# tests.net
KiCad netlist of a schematic drawn in EAGLE
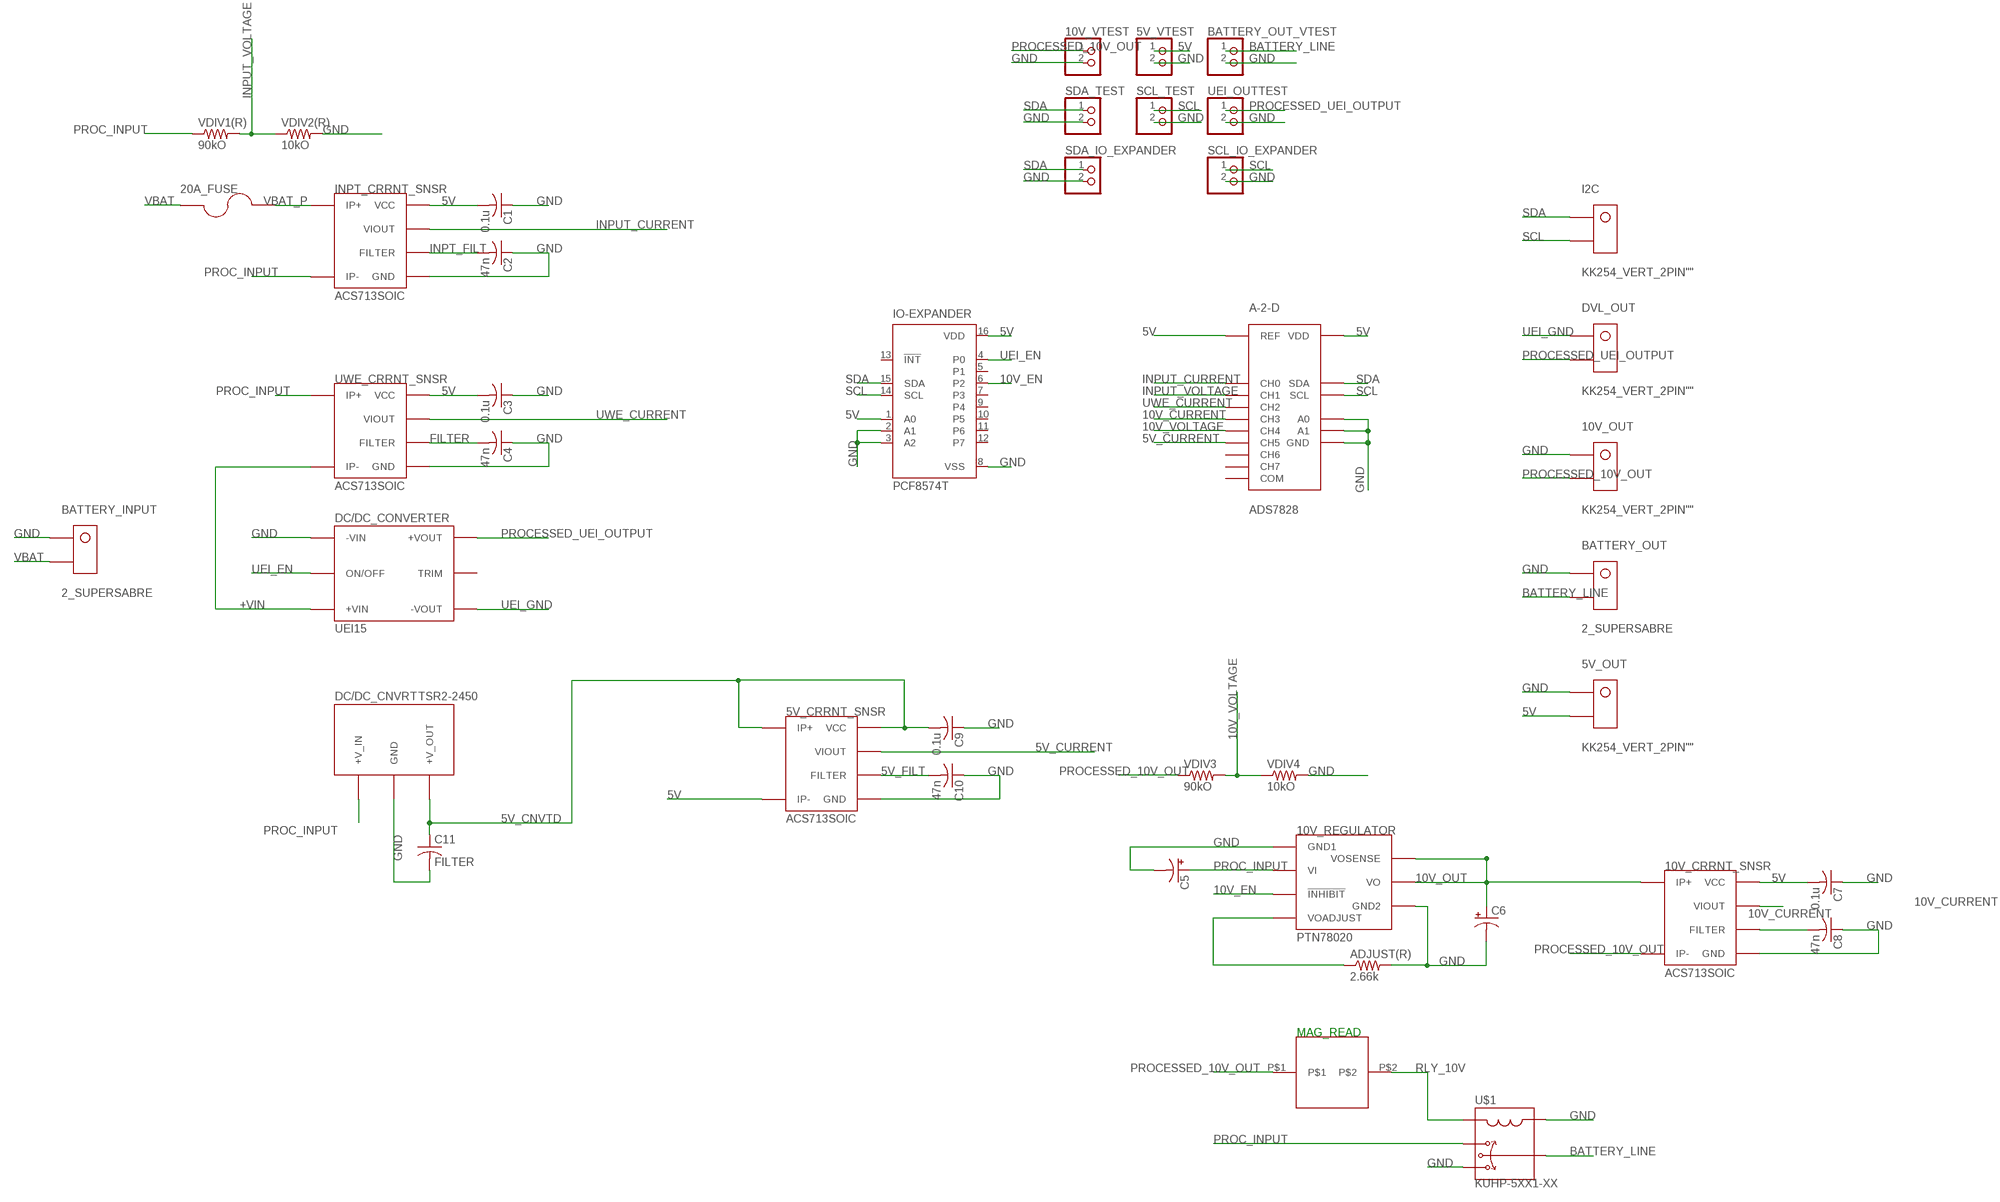
[diagram p0: schematic, sheet 1]

(export (version "E")
  (design (tool "Eeschema 10.0.6"))
  (components
    (comp (ref "5V_CRRNT_SNSR")
      (value "ACS713SOIC")
      (footprint "eagle-import:ACS713-SOIC")
      (libsource (lib "eagle-import") (part "ACS713SOIC"))
    )
    (comp (ref "5V_OUT")
      (value "KK254_VERT_2PIN\"\"")
      (footprint "eagle-import:KK254_VERT_2PIN")
      (libsource (lib "eagle-import") (part "KK254_VERT_2PIN{dblquote}{dblquote}"))
    )
    (comp (ref "5V_VTEST")
      (value "PINHD-1X2")
      (footprint "eagle-import:1X02")
      (libsource (lib "eagle-import") (part "PINHD-1X2"))
    )
    (comp (ref "10V_CRRNT_SNSR")
      (value "ACS713SOIC")
      (footprint "eagle-import:ACS713-SOIC")
      (libsource (lib "eagle-import") (part "ACS713SOIC"))
    )
    (comp (ref "10V_OUT")
      (value "KK254_VERT_2PIN\"\"")
      (footprint "eagle-import:KK254_VERT_2PIN")
      (libsource (lib "eagle-import") (part "KK254_VERT_2PIN{dblquote}{dblquote}"))
    )
    (comp (ref "10V_REGULATOR")
      (value "PTN78020")
      (footprint "eagle-import:PTN")
      (libsource (lib "eagle-import") (part "PTN78020"))
    )
    (comp (ref "10V_VTEST")
      (value "PINHD-1X2")
      (footprint "eagle-import:1X02")
      (libsource (lib "eagle-import") (part "PINHD-1X2"))
    )
    (comp (ref "20A_FUSE")
      (value "BOWED-1.25\"-FUSECLIPS")
      (footprint "eagle-import:1.25__FUSECLIPS")
      (libsource (lib "eagle-import") (part "BOWED-1.25{dblquote}-FUSECLIPS"))
    )
    (comp (ref "A-2-D")
      (value "ADS7828")
      (footprint "eagle-import:TSSOP16")
      (libsource (lib "eagle-import") (part "ADS7828"))
    )
    (comp (ref "ADJUST(R)")
      (value "2.66k")
      (footprint "eagle-import:R0805")
      (libsource (lib "eagle-import") (part "R-US_R0805"))
    )
    (comp (ref "BATTERY_INPUT")
      (value "2_SUPERSABRE")
      (footprint "eagle-import:SUPERSABRE_2CIRCUIT")
      (libsource (lib "eagle-import") (part "2_SUPERSABRE"))
    )
    (comp (ref "BATTERY_OUT")
      (value "2_SUPERSABRE")
      (footprint "eagle-import:SUPERSABRE_2CIRCUIT")
      (libsource (lib "eagle-import") (part "2_SUPERSABRE"))
    )
    (comp (ref "BATTERY_OUT_VTEST")
      (value "PINHD-1X2")
      (footprint "eagle-import:1X02")
      (libsource (lib "eagle-import") (part "PINHD-1X2"))
    )
    (comp (ref "C1")
      (value "0.1u")
      (footprint "eagle-import:C0805")
      (libsource (lib "eagle-import") (part "C-USC0805"))
    )
    (comp (ref "C2")
      (value "47n")
      (footprint "eagle-import:C0805")
      (libsource (lib "eagle-import") (part "C-USC0805"))
    )
    (comp (ref "C3")
      (value "0.1u")
      (footprint "eagle-import:C0805")
      (libsource (lib "eagle-import") (part "C-USC0805"))
    )
    (comp (ref "C4")
      (value "47n")
      (footprint "eagle-import:C0805")
      (libsource (lib "eagle-import") (part "C-USC0805"))
    )
    (comp (ref "C5")
      (value "CPOL-US")
      (footprint "eagle-import:PANASONIC_A_TYPE_M")
      (libsource (lib "eagle-import") (part "CPOL-US"))
    )
    (comp (ref "C6")
      (value "CPOL-US")
      (footprint "eagle-import:PANASONIC_A_TYPE_M")
      (libsource (lib "eagle-import") (part "CPOL-US"))
    )
    (comp (ref "C7")
      (value "0.1u")
      (footprint "eagle-import:C0805")
      (libsource (lib "eagle-import") (part "C-USC0805"))
    )
    (comp (ref "C8")
      (value "47n")
      (footprint "eagle-import:C0805")
      (libsource (lib "eagle-import") (part "C-USC0805"))
    )
    (comp (ref "C9")
      (value "0.1u")
      (footprint "eagle-import:C0805")
      (libsource (lib "eagle-import") (part "C-USC0805"))
    )
    (comp (ref "C10")
      (value "47n")
      (footprint "eagle-import:C0805")
      (libsource (lib "eagle-import") (part "C-USC0805"))
    )
    (comp (ref "C11")
      (value "FILTER")
      (footprint "eagle-import:C0805")
      (libsource (lib "eagle-import") (part "C-USC0805"))
    )
    (comp (ref "DC/DC_CNVRT")
      (value "TSR2-2450")
      (footprint "eagle-import:TSR2")
      (libsource (lib "eagle-import") (part "TSR2-2450"))
    )
    (comp (ref "DC/DC_CONVERTER")
      (value "UEI15")
      (footprint "eagle-import:UEI15")
      (libsource (lib "eagle-import") (part "UEI15"))
    )
    (comp (ref "DVL_OUT")
      (value "KK254_VERT_2PIN\"\"")
      (footprint "eagle-import:KK254_VERT_2PIN")
      (libsource (lib "eagle-import") (part "KK254_VERT_2PIN{dblquote}{dblquote}"))
    )
    (comp (ref "I2C")
      (value "KK254_VERT_2PIN\"\"")
      (footprint "eagle-import:KK254_VERT_2PIN")
      (libsource (lib "eagle-import") (part "KK254_VERT_2PIN{dblquote}{dblquote}"))
    )
    (comp (ref "INPT_CRRNT_SNSR")
      (value "ACS713SOIC")
      (footprint "eagle-import:ACS713-SOIC")
      (libsource (lib "eagle-import") (part "ACS713SOIC"))
    )
    (comp (ref "IO-EXPANDER")
      (value "PCF8574T")
      (footprint "eagle-import:SO16W")
      (fields (field (name "MPN") "PCF8574T/3,512"))
      (libsource (lib "eagle-import") (part "PCF8574T"))
    )
    (comp (ref "MAGREAD")
      (value "HE151TR-ND")
      (footprint "eagle-import:HE151TR-ND")
      (libsource (lib "eagle-import") (part "HE151TR-ND"))
    )
    (comp (ref "SCL_IO_EXPANDER")
      (value "PINHD-1X2")
      (footprint "eagle-import:1X02")
      (libsource (lib "eagle-import") (part "PINHD-1X2"))
    )
    (comp (ref "SCL_TEST")
      (value "PINHD-1X2")
      (footprint "eagle-import:1X02")
      (libsource (lib "eagle-import") (part "PINHD-1X2"))
    )
    (comp (ref "SDA_IO_EXPANDER")
      (value "PINHD-1X2")
      (footprint "eagle-import:1X02")
      (libsource (lib "eagle-import") (part "PINHD-1X2"))
    )
    (comp (ref "SDA_TEST")
      (value "PINHD-1X2")
      (footprint "eagle-import:1X02")
      (libsource (lib "eagle-import") (part "PINHD-1X2"))
    )
    (comp (ref "U$1")
      (value "KUHP-5XX1-XX")
      (footprint "eagle-import:KUHP_6.35MM-QUICK-CONNECT")
      (libsource (lib "eagle-import") (part "KUHP-5XX1-XX"))
    )
    (comp (ref "UEI_OUTTEST")
      (value "PINHD-1X2")
      (footprint "eagle-import:1X02")
      (libsource (lib "eagle-import") (part "PINHD-1X2"))
    )
    (comp (ref "UWE_CRRNT_SNSR")
      (value "ACS713SOIC")
      (footprint "eagle-import:ACS713-SOIC")
      (libsource (lib "eagle-import") (part "ACS713SOIC"))
    )
    (comp (ref "VDIV1(R)")
      (value "90kO")
      (footprint "eagle-import:R0805")
      (libsource (lib "eagle-import") (part "R-US_R0805"))
    )
    (comp (ref "VDIV2(R)")
      (value "10kO")
      (footprint "eagle-import:R0805")
      (libsource (lib "eagle-import") (part "R-US_R0805"))
    )
    (comp (ref "VDIV3")
      (value "90kO")
      (footprint "eagle-import:R0805")
      (libsource (lib "eagle-import") (part "R-US_R0805"))
    )
    (comp (ref "VDIV4")
      (value "10kO")
      (footprint "eagle-import:R0805")
      (libsource (lib "eagle-import") (part "R-US_R0805"))
    )
  )
  (nets
    (net (code "1") (name "/+VIN") (class "Default")
      (node (ref "DC/DC_CONVERTER") (pin "+VIN") (pinfunction "+VIN_+VIN") (pintype "power_in"))
      (node (ref "UWE_CRRNT_SNSR") (pin "P$3") (pinfunction "IP-_P$3") (pintype "bidirectional"))
      (node (ref "UWE_CRRNT_SNSR") (pin "P$4") (pinfunction "IP-_P$4") (pintype "bidirectional"))
    )
    (net (code "2") (name "/5V") (class "Default")
      (node (ref "10V_CRRNT_SNSR") (pin "P$8") (pinfunction "VCC_P$8") (pintype "bidirectional"))
      (node (ref "5V_CRRNT_SNSR") (pin "P$3") (pinfunction "IP-_P$3") (pintype "bidirectional"))
      (node (ref "5V_CRRNT_SNSR") (pin "P$4") (pinfunction "IP-_P$4") (pintype "bidirectional"))
      (node (ref "5V_OUT") (pin "P$2") (pinfunction "P$2_P$2") (pintype "bidirectional"))
      (node (ref "5V_VTEST") (pin "1") (pinfunction "1_1") (pintype "passive"))
      (node (ref "A-2-D") (pin "10") (pinfunction "REF_10") (pintype "bidirectional"))
      (node (ref "A-2-D") (pin "16") (pinfunction "VDD_16") (pintype "bidirectional"))
      (node (ref "C1") (pin "2") (pinfunction "2_2") (pintype "passive"))
      (node (ref "C3") (pin "2") (pinfunction "2_2") (pintype "passive"))
      (node (ref "C7") (pin "2") (pinfunction "2_2") (pintype "passive"))
      (node (ref "INPT_CRRNT_SNSR") (pin "P$8") (pinfunction "VCC_P$8") (pintype "bidirectional"))
      (node (ref "IO-EXPANDER") (pin "1") (pinfunction "A0_1") (pintype "input"))
      (node (ref "IO-EXPANDER") (pin "16") (pinfunction "VDD_16") (pintype "power_in"))
      (node (ref "UWE_CRRNT_SNSR") (pin "P$8") (pinfunction "VCC_P$8") (pintype "bidirectional"))
    )
    (net (code "3") (name "/5V_CNVTD") (class "Default")
      (node (ref "5V_CRRNT_SNSR") (pin "P$1") (pinfunction "IP+_P$1") (pintype "bidirectional"))
      (node (ref "5V_CRRNT_SNSR") (pin "P$2") (pinfunction "IP+_P$2") (pintype "bidirectional"))
      (node (ref "5V_CRRNT_SNSR") (pin "P$8") (pinfunction "VCC_P$8") (pintype "bidirectional"))
      (node (ref "C11") (pin "1") (pinfunction "1_1") (pintype "passive"))
      (node (ref "C9") (pin "2") (pinfunction "2_2") (pintype "passive"))
      (node (ref "DC/DC_CNVRT") (pin "3") (pinfunction "+V_OUT_3") (pintype "power_in"))
    )
    (net (code "4") (name "/5V_CURRENT") (class "Default")
      (node (ref "5V_CRRNT_SNSR") (pin "P$7") (pinfunction "VIOUT_P$7") (pintype "bidirectional"))
      (node (ref "A-2-D") (pin "6") (pinfunction "CH5_6") (pintype "bidirectional"))
    )
    (net (code "5") (name "/5V_FILT") (class "Default")
      (node (ref "5V_CRRNT_SNSR") (pin "P$6") (pinfunction "FILTER_P$6") (pintype "bidirectional"))
      (node (ref "C10") (pin "2") (pinfunction "2_2") (pintype "passive"))
    )
    (net (code "6") (name "/10V_CURRENT") (class "Default")
      (node (ref "10V_CRRNT_SNSR") (pin "P$7") (pinfunction "VIOUT_P$7") (pintype "bidirectional"))
      (node (ref "A-2-D") (pin "4") (pinfunction "CH3_4") (pintype "bidirectional"))
    )
    (net (code "7") (name "/10V_EN") (class "Default")
      (node (ref "10V_REGULATOR") (pin "INHIBIT") (pinfunction "~{INHIBIT}_INHIBIT") (pintype "bidirectional"))
      (node (ref "IO-EXPANDER") (pin "6") (pinfunction "P2_6") (pintype "bidirectional"))
    )
    (net (code "8") (name "/10V_OUT") (class "Default")
      (node (ref "10V_CRRNT_SNSR") (pin "P$1") (pinfunction "IP+_P$1") (pintype "bidirectional"))
      (node (ref "10V_CRRNT_SNSR") (pin "P$2") (pinfunction "IP+_P$2") (pintype "bidirectional"))
      (node (ref "10V_REGULATOR") (pin "SENSE") (pinfunction "VOSENSE_SENSE") (pintype "bidirectional"))
      (node (ref "10V_REGULATOR") (pin "VOUT") (pinfunction "VO_VOUT") (pintype "bidirectional"))
      (node (ref "C6") (pin "+") (pinfunction "+_+") (pintype "passive"))
    )
    (net (code "9") (name "/10V_VOLTAGE") (class "Default")
      (node (ref "A-2-D") (pin "5") (pinfunction "CH4_5") (pintype "bidirectional"))
      (node (ref "VDIV3") (pin "2") (pinfunction "2_2") (pintype "passive"))
      (node (ref "VDIV4") (pin "1") (pinfunction "1_1") (pintype "passive"))
    )
    (net (code "10") (name "/BATTERY_LINE") (class "Default")
      (node (ref "BATTERY_OUT") (pin "P$2") (pinfunction "P$2_P$2") (pintype "bidirectional"))
      (node (ref "BATTERY_OUT_VTEST") (pin "1") (pinfunction "1_1") (pintype "passive"))
      (node (ref "U$1") (pin "7A") (pinfunction "7_7A") (pintype "bidirectional"))
      (node (ref "U$1") (pin "7B") (pinfunction "7_7B") (pintype "bidirectional"))
    )
    (net (code "11") (name "/FILTER") (class "Default")
      (node (ref "C4") (pin "2") (pinfunction "2_2") (pintype "passive"))
      (node (ref "UWE_CRRNT_SNSR") (pin "P$6") (pinfunction "FILTER_P$6") (pintype "bidirectional"))
    )
    (net (code "12") (name "/GND") (class "Default")
      (node (ref "10V_CRRNT_SNSR") (pin "P$5") (pinfunction "GND_P$5") (pintype "bidirectional"))
      (node (ref "10V_OUT") (pin "P$1") (pinfunction "P$1_P$1") (pintype "bidirectional"))
      (node (ref "10V_REGULATOR") (pin "GND1") (pinfunction "GND1_GND1") (pintype "bidirectional"))
      (node (ref "10V_REGULATOR") (pin "GND2") (pinfunction "GND2_GND2") (pintype "bidirectional"))
      (node (ref "10V_VTEST") (pin "2") (pinfunction "2_2") (pintype "passive"))
      (node (ref "5V_CRRNT_SNSR") (pin "P$5") (pinfunction "GND_P$5") (pintype "bidirectional"))
      (node (ref "5V_OUT") (pin "P$1") (pinfunction "P$1_P$1") (pintype "bidirectional"))
      (node (ref "5V_VTEST") (pin "2") (pinfunction "2_2") (pintype "passive"))
      (node (ref "A-2-D") (pin "12") (pinfunction "A0_12") (pintype "bidirectional"))
      (node (ref "A-2-D") (pin "13") (pinfunction "A1_13") (pintype "bidirectional"))
      (node (ref "A-2-D") (pin "9") (pinfunction "GND_9") (pintype "bidirectional"))
      (node (ref "ADJUST(R)") (pin "2") (pinfunction "2_2") (pintype "passive"))
      (node (ref "BATTERY_INPUT") (pin "P$1") (pinfunction "P$1_P$1") (pintype "bidirectional"))
      (node (ref "BATTERY_OUT") (pin "P$1") (pinfunction "P$1_P$1") (pintype "bidirectional"))
      (node (ref "BATTERY_OUT_VTEST") (pin "2") (pinfunction "2_2") (pintype "passive"))
      (node (ref "C1") (pin "1") (pinfunction "1_1") (pintype "passive"))
      (node (ref "C10") (pin "1") (pinfunction "1_1") (pintype "passive"))
      (node (ref "C11") (pin "2") (pinfunction "2_2") (pintype "passive"))
      (node (ref "C2") (pin "1") (pinfunction "1_1") (pintype "passive"))
      (node (ref "C3") (pin "1") (pinfunction "1_1") (pintype "passive"))
      (node (ref "C4") (pin "1") (pinfunction "1_1") (pintype "passive"))
      (node (ref "C5") (pin "-") (pinfunction "-_-") (pintype "passive"))
      (node (ref "C6") (pin "-") (pinfunction "-_-") (pintype "passive"))
      (node (ref "C7") (pin "1") (pinfunction "1_1") (pintype "passive"))
      (node (ref "C8") (pin "1") (pinfunction "1_1") (pintype "passive"))
      (node (ref "C9") (pin "1") (pinfunction "1_1") (pintype "passive"))
      (node (ref "DC/DC_CNVRT") (pin "2") (pinfunction "GND_2") (pintype "power_in"))
      (node (ref "DC/DC_CONVERTER") (pin "-VIN") (pinfunction "-VIN_-VIN") (pintype "power_in"))
      (node (ref "INPT_CRRNT_SNSR") (pin "P$5") (pinfunction "GND_P$5") (pintype "bidirectional"))
      (node (ref "IO-EXPANDER") (pin "2") (pinfunction "A1_2") (pintype "input"))
      (node (ref "IO-EXPANDER") (pin "3") (pinfunction "A2_3") (pintype "input"))
      (node (ref "IO-EXPANDER") (pin "8") (pinfunction "VSS_8") (pintype "power_in"))
      (node (ref "SCL_IO_EXPANDER") (pin "2") (pinfunction "2_2") (pintype "passive"))
      (node (ref "SCL_TEST") (pin "2") (pinfunction "2_2") (pintype "passive"))
      (node (ref "SDA_IO_EXPANDER") (pin "2") (pinfunction "2_2") (pintype "passive"))
      (node (ref "SDA_TEST") (pin "2") (pinfunction "2_2") (pintype "passive"))
      (node (ref "U$1") (pin "5A") (pinfunction "5_5A") (pintype "bidirectional"))
      (node (ref "U$1") (pin "5B") (pinfunction "5_5B") (pintype "bidirectional"))
      (node (ref "U$1") (pin "AA") (pinfunction "A_AA") (pintype "bidirectional"))
      (node (ref "U$1") (pin "AB") (pinfunction "A_AB") (pintype "bidirectional"))
      (node (ref "UEI_OUTTEST") (pin "2") (pinfunction "2_2") (pintype "passive"))
      (node (ref "UWE_CRRNT_SNSR") (pin "P$5") (pinfunction "GND_P$5") (pintype "bidirectional"))
      (node (ref "VDIV2(R)") (pin "2") (pinfunction "2_2") (pintype "passive"))
      (node (ref "VDIV4") (pin "2") (pinfunction "2_2") (pintype "passive"))
    )
    (net (code "13") (name "/INPT_FILT") (class "Default")
      (node (ref "C2") (pin "2") (pinfunction "2_2") (pintype "passive"))
      (node (ref "INPT_CRRNT_SNSR") (pin "P$6") (pinfunction "FILTER_P$6") (pintype "bidirectional"))
    )
    (net (code "14") (name "/INPUT_CURRENT") (class "Default")
      (node (ref "A-2-D") (pin "1") (pinfunction "CH0_1") (pintype "bidirectional"))
      (node (ref "INPT_CRRNT_SNSR") (pin "P$7") (pinfunction "VIOUT_P$7") (pintype "bidirectional"))
    )
    (net (code "15") (name "/INPUT_VOLTAGE") (class "Default")
      (node (ref "A-2-D") (pin "2") (pinfunction "CH1_2") (pintype "bidirectional"))
      (node (ref "VDIV1(R)") (pin "2") (pinfunction "2_2") (pintype "passive"))
      (node (ref "VDIV2(R)") (pin "1") (pinfunction "1_1") (pintype "passive"))
    )
    (net (code "16") (name "/PROCESSED_10V_OUT") (class "Default")
      (node (ref "10V_CRRNT_SNSR") (pin "P$3") (pinfunction "IP-_P$3") (pintype "bidirectional"))
      (node (ref "10V_CRRNT_SNSR") (pin "P$4") (pinfunction "IP-_P$4") (pintype "bidirectional"))
      (node (ref "10V_OUT") (pin "P$2") (pinfunction "P$2_P$2") (pintype "bidirectional"))
      (node (ref "10V_VTEST") (pin "1") (pinfunction "1_1") (pintype "passive"))
      (node (ref "MAGREAD") (pin "P$1") (pinfunction "P$1_P$1") (pintype "bidirectional"))
      (node (ref "VDIV3") (pin "1") (pinfunction "1_1") (pintype "passive"))
    )
    (net (code "17") (name "/PROCESSED_UEI_OUTPUT") (class "Default")
      (node (ref "DC/DC_CONVERTER") (pin "+VOUT") (pinfunction "+VOUT_+VOUT") (pintype "power_in"))
      (node (ref "DVL_OUT") (pin "P$2") (pinfunction "P$2_P$2") (pintype "bidirectional"))
      (node (ref "UEI_OUTTEST") (pin "1") (pinfunction "1_1") (pintype "passive"))
    )
    (net (code "18") (name "/PROC_INPUT") (class "Default")
      (node (ref "10V_REGULATOR") (pin "VIN") (pinfunction "VI_VIN") (pintype "bidirectional"))
      (node (ref "C5") (pin "+") (pinfunction "+_+") (pintype "passive"))
      (node (ref "DC/DC_CNVRT") (pin "1") (pinfunction "+V_IN_1") (pintype "power_in"))
      (node (ref "INPT_CRRNT_SNSR") (pin "P$3") (pinfunction "IP-_P$3") (pintype "bidirectional"))
      (node (ref "INPT_CRRNT_SNSR") (pin "P$4") (pinfunction "IP-_P$4") (pintype "bidirectional"))
      (node (ref "U$1") (pin "2A") (pinfunction "2_2A") (pintype "bidirectional"))
      (node (ref "U$1") (pin "2B") (pinfunction "2_2B") (pintype "bidirectional"))
      (node (ref "UWE_CRRNT_SNSR") (pin "P$1") (pinfunction "IP+_P$1") (pintype "bidirectional"))
      (node (ref "UWE_CRRNT_SNSR") (pin "P$2") (pinfunction "IP+_P$2") (pintype "bidirectional"))
      (node (ref "VDIV1(R)") (pin "1") (pinfunction "1_1") (pintype "passive"))
    )
    (net (code "19") (name "/RLY_10V") (class "Default")
      (node (ref "MAGREAD") (pin "P$2") (pinfunction "P$2_P$2") (pintype "bidirectional"))
      (node (ref "U$1") (pin "BA") (pinfunction "B_BA") (pintype "bidirectional"))
      (node (ref "U$1") (pin "BB") (pinfunction "B_BB") (pintype "bidirectional"))
    )
    (net (code "20") (name "/SCL") (class "Default")
      (node (ref "A-2-D") (pin "14") (pinfunction "SCL_14") (pintype "bidirectional"))
      (node (ref "I2C") (pin "P$2") (pinfunction "P$2_P$2") (pintype "bidirectional"))
      (node (ref "IO-EXPANDER") (pin "14") (pinfunction "SCL_14") (pintype "input"))
      (node (ref "SCL_IO_EXPANDER") (pin "1") (pinfunction "1_1") (pintype "passive"))
      (node (ref "SCL_TEST") (pin "1") (pinfunction "1_1") (pintype "passive"))
    )
    (net (code "21") (name "/SDA") (class "Default")
      (node (ref "A-2-D") (pin "15") (pinfunction "SDA_15") (pintype "bidirectional"))
      (node (ref "I2C") (pin "P$1") (pinfunction "P$1_P$1") (pintype "bidirectional"))
      (node (ref "IO-EXPANDER") (pin "15") (pinfunction "SDA_15") (pintype "bidirectional"))
      (node (ref "SDA_IO_EXPANDER") (pin "1") (pinfunction "1_1") (pintype "passive"))
      (node (ref "SDA_TEST") (pin "1") (pinfunction "1_1") (pintype "passive"))
    )
    (net (code "22") (name "/UEI_EN") (class "Default")
      (node (ref "DC/DC_CONVERTER") (pin "ON/OFFCNTRL") (pinfunction "ON/OFF_ON/OFFCNTRL") (pintype "bidirectional"))
      (node (ref "IO-EXPANDER") (pin "4") (pinfunction "P0_4") (pintype "bidirectional"))
    )
    (net (code "23") (name "/UEI_GND") (class "Default")
      (node (ref "DC/DC_CONVERTER") (pin "-VOUT") (pinfunction "-VOUT_-VOUT") (pintype "power_in"))
      (node (ref "DVL_OUT") (pin "P$1") (pinfunction "P$1_P$1") (pintype "bidirectional"))
    )
    (net (code "24") (name "/UWE_CURRENT") (class "Default")
      (node (ref "A-2-D") (pin "3") (pinfunction "CH2_3") (pintype "bidirectional"))
      (node (ref "UWE_CRRNT_SNSR") (pin "P$7") (pinfunction "VIOUT_P$7") (pintype "bidirectional"))
    )
    (net (code "25") (name "/VBAT") (class "Default")
      (node (ref "20A_FUSE") (pin "P$1") (pinfunction "P$1_P$1") (pintype "bidirectional"))
      (node (ref "20A_FUSE") (pin "P$2") (pinfunction "P$1_P$2") (pintype "bidirectional"))
      (node (ref "BATTERY_INPUT") (pin "P$2") (pinfunction "P$2_P$2") (pintype "bidirectional"))
    )
    (net (code "26") (name "/VBAT_P") (class "Default")
      (node (ref "20A_FUSE") (pin "P$3") (pinfunction "P$2_P$3") (pintype "bidirectional"))
      (node (ref "20A_FUSE") (pin "P$4") (pinfunction "P$2_P$4") (pintype "bidirectional"))
      (node (ref "INPT_CRRNT_SNSR") (pin "P$1") (pinfunction "IP+_P$1") (pintype "bidirectional"))
      (node (ref "INPT_CRRNT_SNSR") (pin "P$2") (pinfunction "IP+_P$2") (pintype "bidirectional"))
    )
    (net (code "27") (name "Net-(10V_CRRNT_SNSR-FILTER)") (class "Default")
      (node (ref "10V_CRRNT_SNSR") (pin "P$6") (pinfunction "FILTER_P$6") (pintype "bidirectional"))
      (node (ref "C8") (pin "2") (pinfunction "2_2") (pintype "passive"))
    )
    (net (code "28") (name "Net-(10V_REGULATOR-VOADJUST)") (class "Default")
      (node (ref "10V_REGULATOR") (pin "ADJUST") (pinfunction "VOADJUST_ADJUST") (pintype "bidirectional"))
      (node (ref "ADJUST(R)") (pin "1") (pinfunction "1_1") (pintype "passive"))
    )
    (net (code "29") (name "unconnected-(A-2-D-CH6-Pad7)") (class "Default")
      (node (ref "A-2-D") (pin "7") (pinfunction "CH6_7") (pintype "bidirectional"))
    )
    (net (code "30") (name "unconnected-(A-2-D-CH7-Pad8)") (class "Default")
      (node (ref "A-2-D") (pin "8") (pinfunction "CH7_8") (pintype "bidirectional"))
    )
    (net (code "31") (name "unconnected-(A-2-D-COM-Pad11)") (class "Default")
      (node (ref "A-2-D") (pin "11") (pinfunction "COM_11") (pintype "bidirectional"))
    )
    (net (code "32") (name "unconnected-(DC/DC_CONVERTER-TRIM-PadOTPTTRIM)") (class "Default")
      (node (ref "DC/DC_CONVERTER") (pin "OTPTTRIM") (pinfunction "TRIM_OTPTTRIM") (pintype "bidirectional"))
    )
    (net (code "33") (name "unconnected-(IO-EXPANDER-P1-Pad5)") (class "Default")
      (node (ref "IO-EXPANDER") (pin "5") (pinfunction "P1_5") (pintype "bidirectional"))
    )
    (net (code "34") (name "unconnected-(IO-EXPANDER-P3-Pad7)") (class "Default")
      (node (ref "IO-EXPANDER") (pin "7") (pinfunction "P3_7") (pintype "bidirectional"))
    )
    (net (code "35") (name "unconnected-(IO-EXPANDER-P4-Pad9)") (class "Default")
      (node (ref "IO-EXPANDER") (pin "9") (pinfunction "P4_9") (pintype "bidirectional"))
    )
    (net (code "36") (name "unconnected-(IO-EXPANDER-P5-Pad10)") (class "Default")
      (node (ref "IO-EXPANDER") (pin "10") (pinfunction "P5_10") (pintype "bidirectional"))
    )
    (net (code "37") (name "unconnected-(IO-EXPANDER-P6-Pad11)") (class "Default")
      (node (ref "IO-EXPANDER") (pin "11") (pinfunction "P6_11") (pintype "bidirectional"))
    )
    (net (code "38") (name "unconnected-(IO-EXPANDER-P7-Pad12)") (class "Default")
      (node (ref "IO-EXPANDER") (pin "12") (pinfunction "P7_12") (pintype "bidirectional"))
    )
    (net (code "39") (name "unconnected-(IO-EXPANDER-~{INT}-Pad13)") (class "Default")
      (node (ref "IO-EXPANDER") (pin "13") (pinfunction "~{INT}_13") (pintype "output"))
    )
  )
)
